# ESP32_with_USBC.net
KiCad netlist of a schematic drawn in Altium Designer
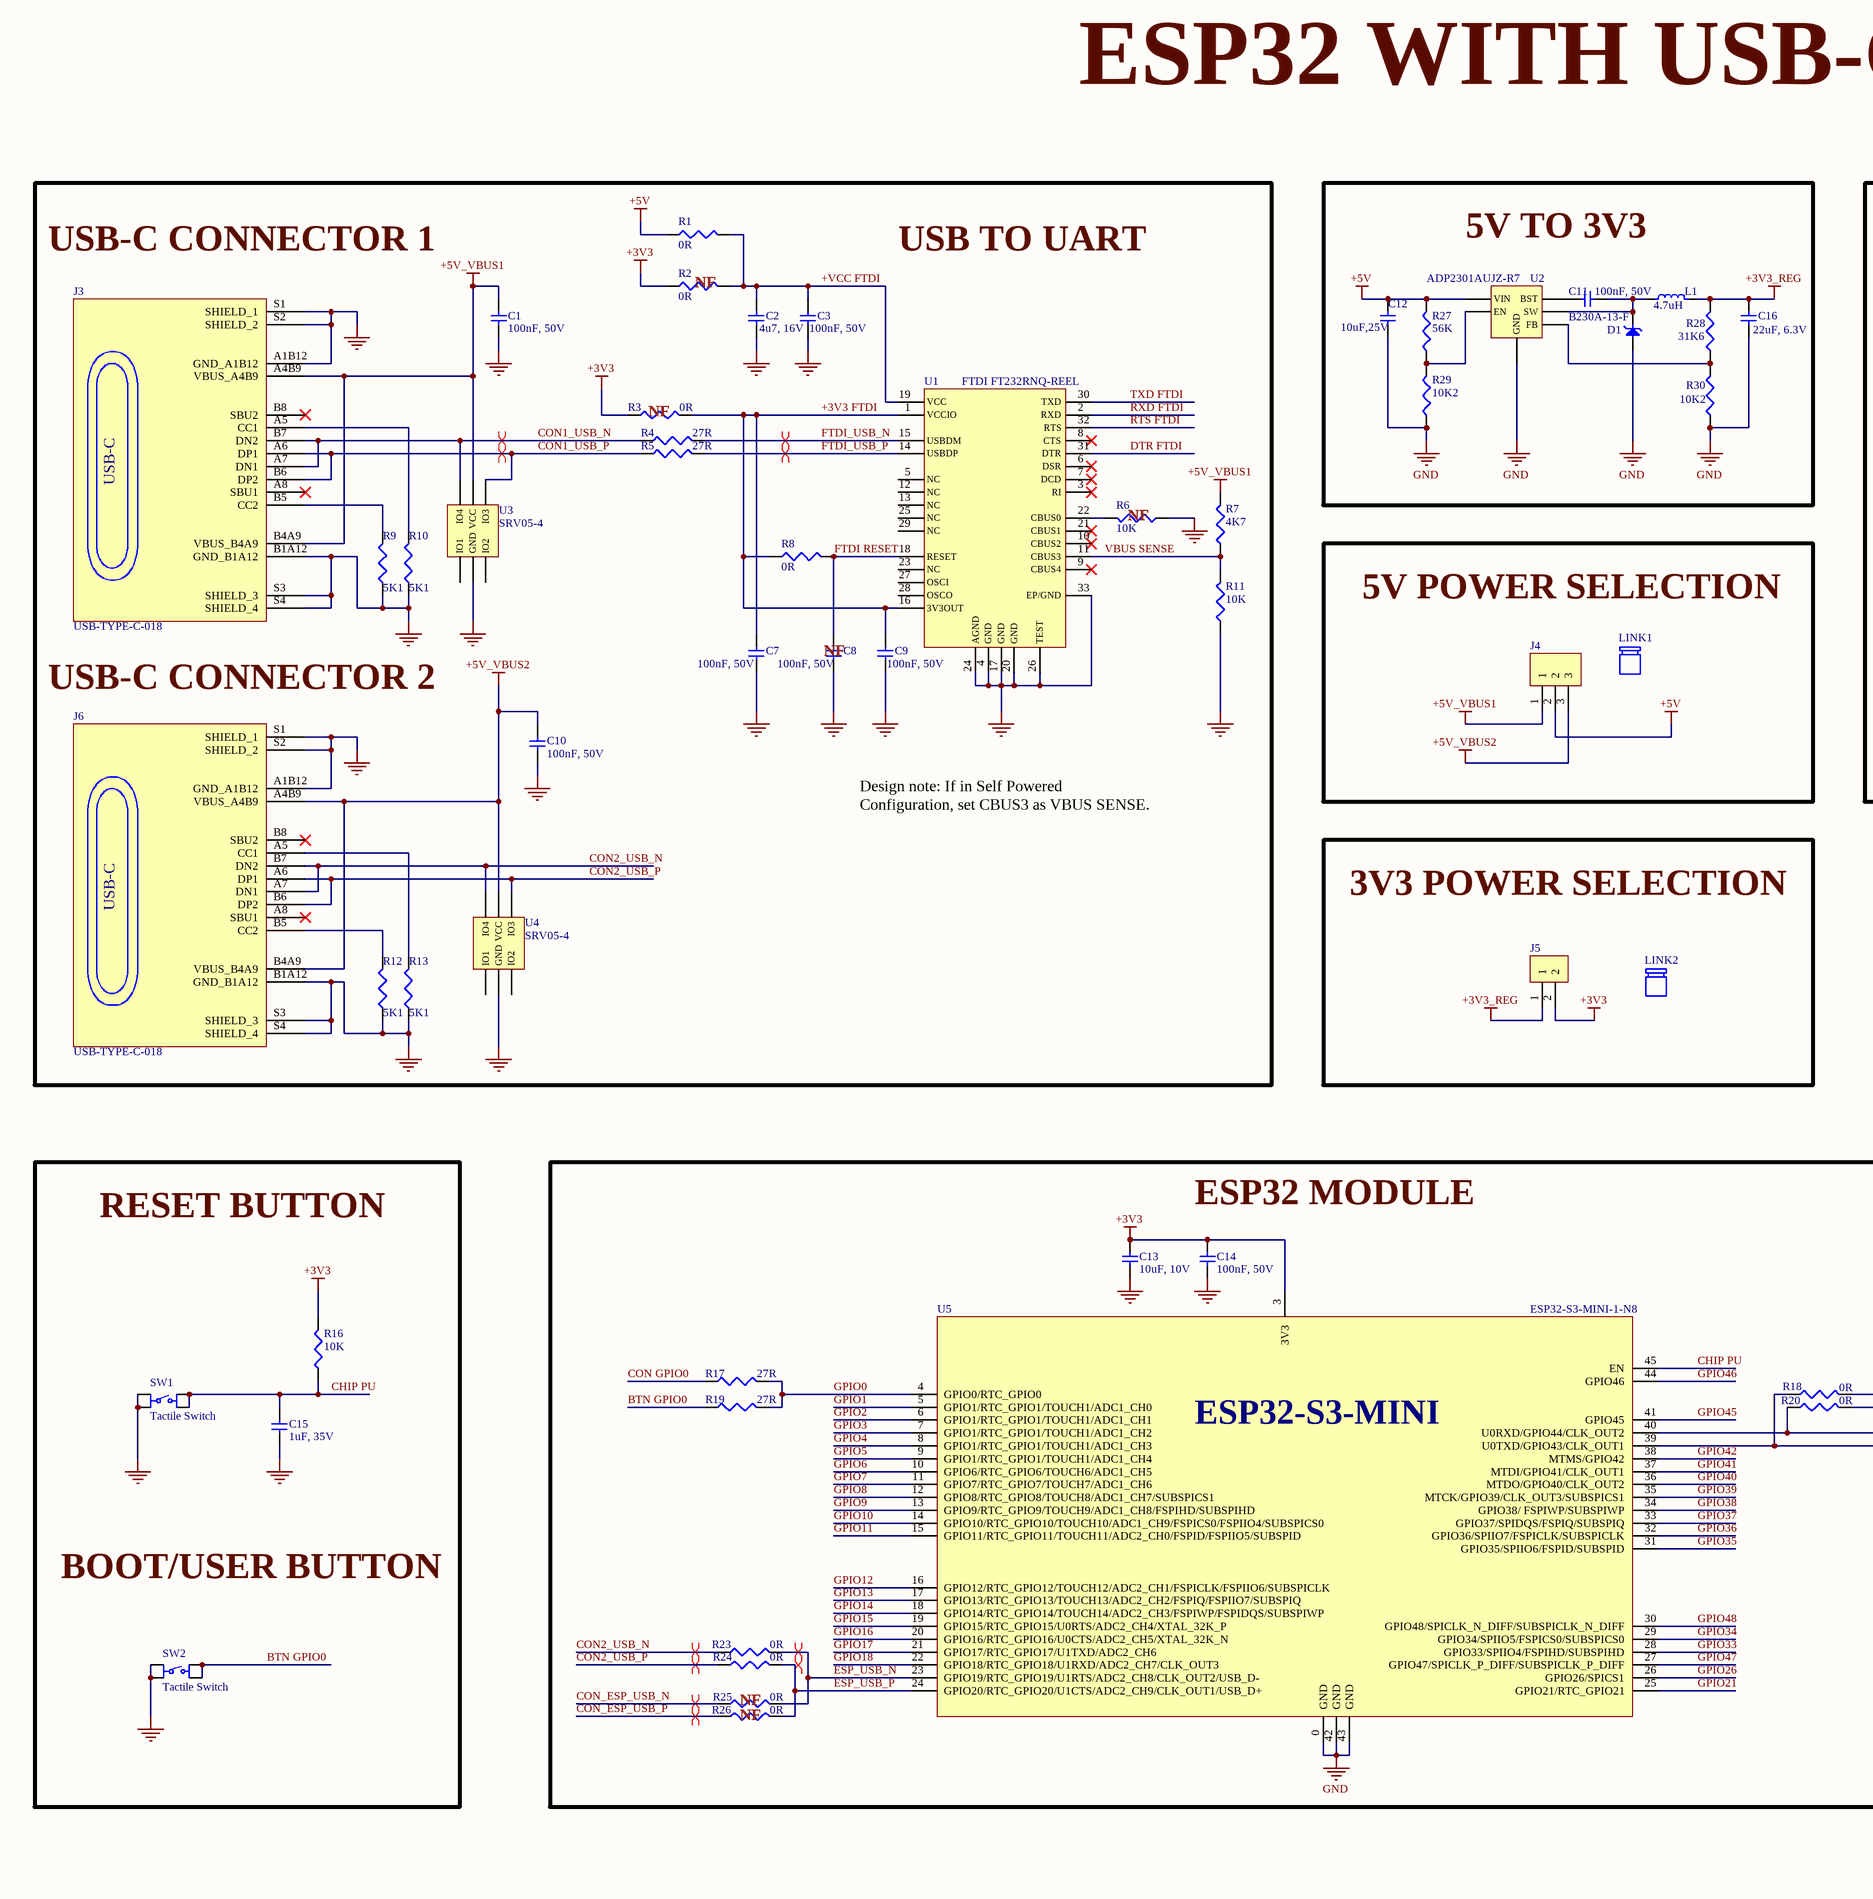
[diagram p0: ESP32 with USBC.SchDoc, left]
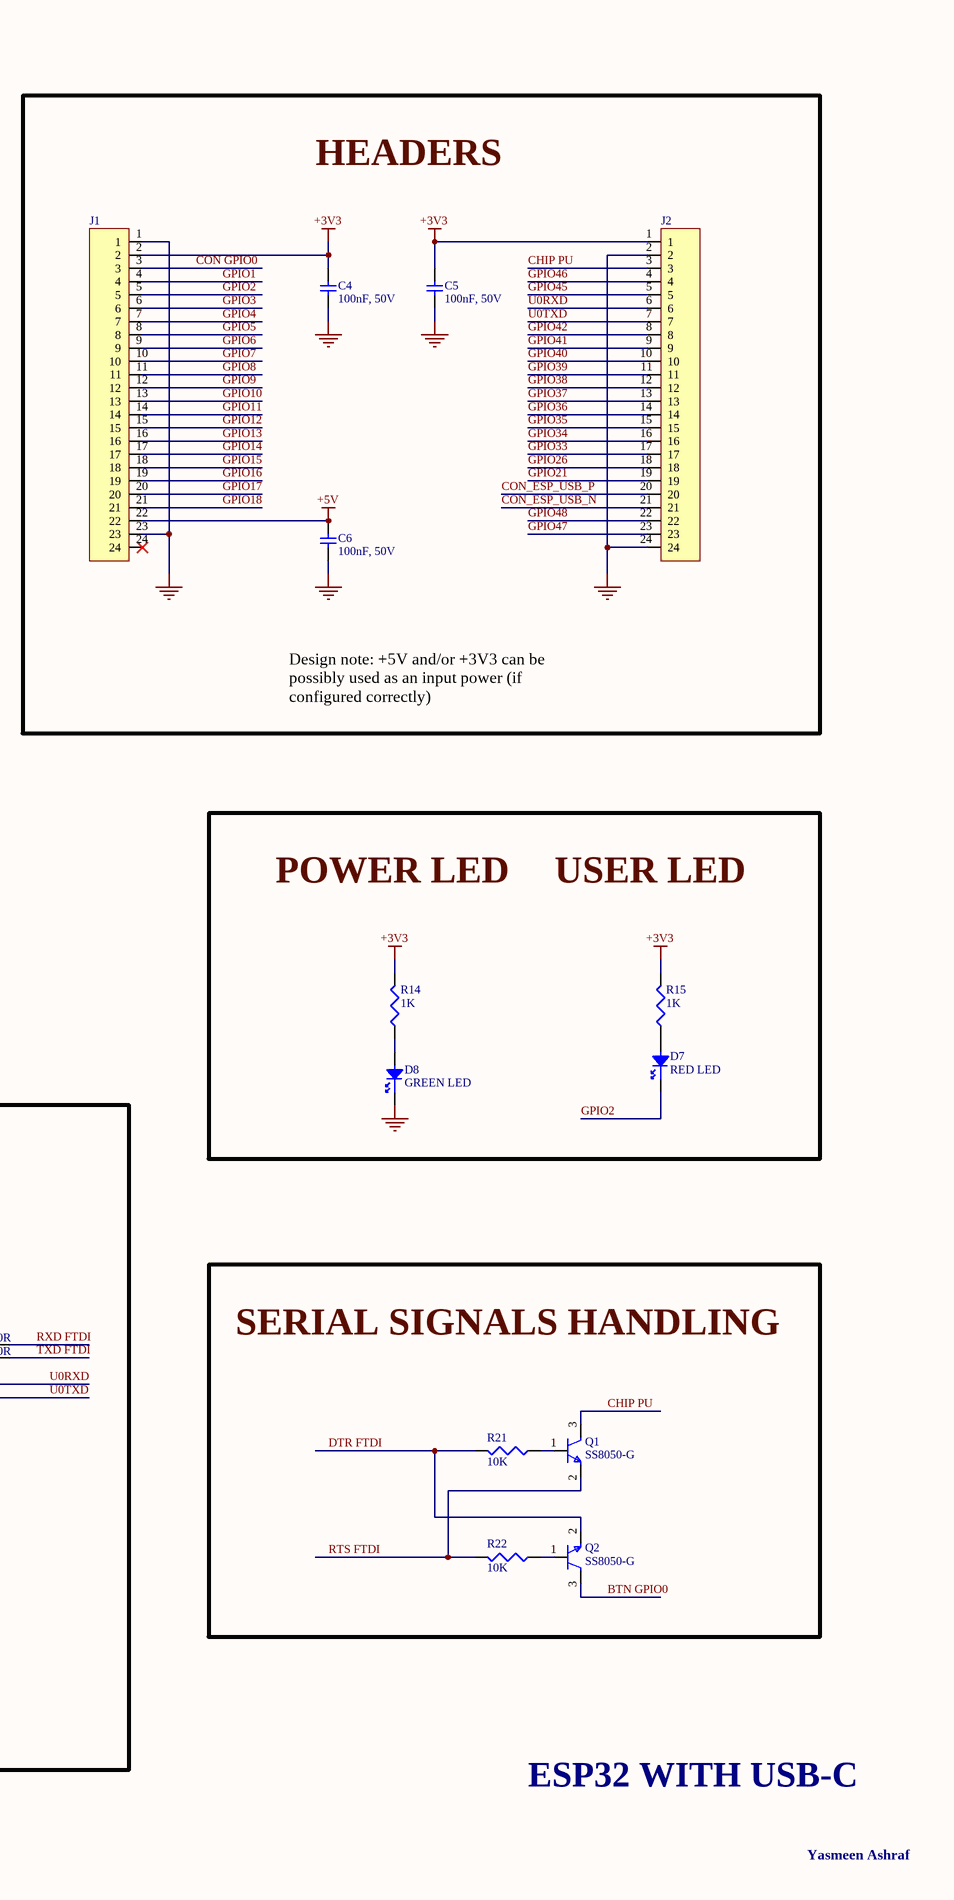
[diagram p1: ESP32 with USBC.SchDoc, right]

(export (version "E")
  (design (tool "Eeschema 10.0.6"))
  (components
    (comp (ref "C1")
      (value "100nF, 50V")
      (footprint "Capacitor")
      (description "50V 100nF X7R ±10% 0402 Multilayer Ceramic Capacitors MLCC - SMD/SMT ROHS")
      (fields
        (field (name "MANUFACTURER") "Samsung")
        (field (name "MANUFACTURER PART NUMBER") "CL05B104KB54PNC")
      )
      (libsource (lib "Schlib1") (part "CL05B104KB54PNC"))
    )
    (comp (ref "C2")
      (value "4u7, 16V")
      (footprint "Capacitor")
      (description "16V 4.7uF X5R ±20% 0402 Multilayer Ceramic Capacitors MLCC - SMD/SMT ROHS")
      (fields
        (field (name "MANUFACTURER") "Samsung Electro-Mechanics")
        (field (name "MANUFACTURER PART NUMBER") "CL05A475MO5NUNC")
      )
      (libsource (lib "Schlib1") (part "CL05A475MO5NUNC"))
    )
    (comp (ref "C3")
      (value "100nF, 50V")
      (footprint "Capacitor")
      (description "50V 100nF X7R ±10% 0402 Multilayer Ceramic Capacitors MLCC - SMD/SMT ROHS")
      (fields
        (field (name "MANUFACTURER") "Samsung")
        (field (name "MANUFACTURER PART NUMBER") "CL05B104KB54PNC")
      )
      (libsource (lib "Schlib1") (part "CL05B104KB54PNC"))
    )
    (comp (ref "C4")
      (value "100nF, 50V")
      (footprint "Capacitor")
      (description "50V 100nF X7R ±10% 0402 Multilayer Ceramic Capacitors MLCC - SMD/SMT ROHS")
      (fields
        (field (name "MANUFACTURER") "Samsung")
        (field (name "MANUFACTURER PART NUMBER") "CL05B104KB54PNC")
      )
      (libsource (lib "Schlib1") (part "CL05B104KB54PNC"))
    )
    (comp (ref "C5")
      (value "100nF, 50V")
      (footprint "Capacitor")
      (description "50V 100nF X7R ±10% 0402 Multilayer Ceramic Capacitors MLCC - SMD/SMT ROHS")
      (fields
        (field (name "MANUFACTURER") "Samsung")
        (field (name "MANUFACTURER PART NUMBER") "CL05B104KB54PNC")
      )
      (libsource (lib "Schlib1") (part "CL05B104KB54PNC"))
    )
    (comp (ref "C6")
      (value "100nF, 50V")
      (footprint "Capacitor")
      (description "50V 100nF X7R ±10% 0402 Multilayer Ceramic Capacitors MLCC - SMD/SMT ROHS")
      (fields
        (field (name "MANUFACTURER") "Samsung")
        (field (name "MANUFACTURER PART NUMBER") "CL05B104KB54PNC")
      )
      (libsource (lib "Schlib1") (part "CL05B104KB54PNC"))
    )
    (comp (ref "C7")
      (value "100nF, 50V")
      (footprint "Capacitor")
      (description "50V 100nF X7R ±10% 0402 Multilayer Ceramic Capacitors MLCC - SMD/SMT ROHS")
      (fields
        (field (name "MANUFACTURER") "Samsung")
        (field (name "MANUFACTURER PART NUMBER") "CL05B104KB54PNC")
      )
      (libsource (lib "Schlib1") (part "CL05B104KB54PNC"))
    )
    (comp (ref "C8")
      (value "100nF, 50V")
      (footprint "Capacitor")
      (description "50V 100nF X7R ±10% 0402 Multilayer Ceramic Capacitors MLCC - SMD/SMT ROHS")
      (fields
        (field (name "MANUFACTURER") "Samsung")
        (field (name "MANUFACTURER PART NUMBER") "CL05B104KB54PNC")
      )
      (libsource (lib "Schlib1") (part "CL05B104KB54PNC"))
    )
    (comp (ref "C9")
      (value "100nF, 50V")
      (footprint "Capacitor")
      (description "50V 100nF X7R ±10% 0402 Multilayer Ceramic Capacitors MLCC - SMD/SMT ROHS")
      (fields
        (field (name "MANUFACTURER") "Samsung")
        (field (name "MANUFACTURER PART NUMBER") "CL05B104KB54PNC")
      )
      (libsource (lib "Schlib1") (part "CL05B104KB54PNC"))
    )
    (comp (ref "C10")
      (value "100nF, 50V")
      (footprint "Capacitor")
      (description "50V 100nF X7R ±10% 0402 Multilayer Ceramic Capacitors MLCC - SMD/SMT ROHS")
      (fields
        (field (name "MANUFACTURER") "Samsung")
        (field (name "MANUFACTURER PART NUMBER") "CL05B104KB54PNC")
      )
      (libsource (lib "Schlib1") (part "CL05B104KB54PNC"))
    )
    (comp (ref "C11")
      (value "100nF, 50V")
      (footprint "Capacitor")
      (description "50V 100nF X7R ±10% 0402 Multilayer Ceramic Capacitors MLCC - SMD/SMT ROHS")
      (fields
        (field (name "MANUFACTURER") "Samsung")
        (field (name "MANUFACTURER PART NUMBER") "CL05B104KB54PNC")
      )
      (libsource (lib "Schlib1") (part "CL05B104KB54PNC"))
    )
    (comp (ref "C12")
      (value "10uF,25V")
      (footprint "CL10A106MA8NRNC")
      (description "25V 10uF X5R ±20% 0603 Multilayer Ceramic Capacitors MLCC - SMD/SMT ROHS")
      (fields
        (field (name "MANUFACTURER") "Samsung Electro-Mechanics")
        (field (name "MANUFACTURER PART NUMBER") "CL10A106MA8NRNC")
      )
      (libsource (lib "Schlib1") (part "CL10A106MA8NRNC"))
    )
    (comp (ref "C13")
      (value "10uF, 10V")
      (footprint "Capacitor")
      (description "10V 10uF X5R ±20% 0402 Multilayer Ceramic Capacitors MLCC - SMD/SMT ROHS")
      (fields
        (field (name "MANUFACTURER") "Samsung")
        (field (name "MANUFACTURER PART NUMBER") "CL05A106MP8NUB8")
      )
      (libsource (lib "Schlib1") (part "CL05A106MP8NUB8"))
    )
    (comp (ref "C14")
      (value "100nF, 50V")
      (footprint "Capacitor")
      (description "50V 100nF X7R ±10% 0402 Multilayer Ceramic Capacitors MLCC - SMD/SMT ROHS")
      (fields
        (field (name "MANUFACTURER") "Samsung")
        (field (name "MANUFACTURER PART NUMBER") "CL05B104KB54PNC")
      )
      (libsource (lib "Schlib1") (part "CL05B104KB54PNC"))
    )
    (comp (ref "C15")
      (value "1uF, 35V")
      (footprint "Capacitor")
      (description "35V 1uF X5R ±10% 0402 Multilayer Ceramic Capacitors MLCC - SMD/SMT ROHS")
      (fields
        (field (name "MANUFACTURER") "Samsung")
        (field (name "MANUFACTURER PART NUMBER") "CL05A105KL5NRNC")
      )
      (libsource (lib "Schlib1") (part "CL05A105KL5NRNC"))
    )
    (comp (ref "C16")
      (value "22uF, 6.3V")
      (footprint "Capacitor")
      (description "6.3V 22uF X5R ±20% 0402 Multilayer Ceramic Capacitors MLCC - SMD/SMT ROHS")
      (fields
        (field (name "MANUFACTURER") "Samsung Electro-Mechanics")
        (field (name "MANUFACTURER PART NUMBER") "CL05A226MQ5QUNC")
      )
      (libsource (lib "Schlib1") (part "CL05A226MQ5QUNC"))
    )
    (comp (ref "D1")
      (value "B230A-13-F")
      (footprint "Schottky Diode")
      (description "30V 500mV@2A 2A SMA(DO-214AC) Schottky Diodes ROHS")
      (fields (field (name "MANUFACTURER") "Diodes Incorporated"))
      (libsource (lib "Schlib1") (part "B230A-13-F"))
    )
    (comp (ref "D7")
      (value "RED LED")
      (footprint "RED LED")
      (description "20mA 54mcd -30℃~+85℃ 631nm Red 130° 75mW 2V 0402 LED Indication - Discrete ROHS")
      (fields (field (name "MANUFACTURE PART NUMBER") "VLMS1500-GS08"))
      (libsource (lib "Schlib1") (part "VLMS1500-GS08"))
    )
    (comp (ref "D8")
      (value "GREEN LED")
      (footprint "GREEN LED")
      (description "20mA 35mcd 571nm Yellow Green 130° 2V 0402 LED Indication - Discrete ROHS")
      (fields (field (name "MANUFACTURE PART NUMBER") "VLMG1500-GS08"))
      (libsource (lib "Schlib1") (part "VLMG1500-GS08"))
    )
    (comp (ref "J1")
      (value "X6511WV-24H-C60D30")
      (footprint "HDR_1x24")
      (libsource (lib "Schlib1") (part "X6511WV-24H-C60D30"))
    )
    (comp (ref "J2")
      (value "X6511WV-24H-C60D30")
      (footprint "HDR_1x24")
      (libsource (lib "") (part "X6511WV-24H-C60D30_1"))
    )
    (comp (ref "J3")
      (value "USB-TYPE-C-018")
      (footprint "USB-TYPE-C-018")
      (description "3A 1 Horizontal attachment 16P Female -25℃~+85℃ Type-C SMD USB Connectors ROHS")
      (libsource (lib "Schlib1") (part "USB-TYPE-C-018"))
    )
    (comp (ref "J4")
      (value "TSW-103-14-G-S")
      (footprint "TSW-103-14-G-S")
      (fields (field (name "MANUFACTURER") "Samtec"))
      (libsource (lib "Schlib1") (part "TSW-103-14-G-S"))
    )
    (comp (ref "J5")
      (value "22284020")
      (footprint "HDR_1x2")
      (description "Direct Insert Policy 2P 2.54mm Single Row Black Brass 1x2P Plugin,P=2.54mm Pin Headers ROHS")
      (libsource (lib "Schlib1") (part "22284020"))
    )
    (comp (ref "J6")
      (value "USB-TYPE-C-018")
      (footprint "USB-TYPE-C-018")
      (description "3A 1 Horizontal attachment 16P Female -25℃~+85℃ Type-C SMD USB Connectors ROHS")
      (libsource (lib "Schlib1") (part "USB-TYPE-C-018"))
    )
    (comp (ref "L1")
      (value "4.7uH")
      (footprint "Inductor")
      (description "2A 4.7uH ±30% 3A SMD,5x5mm Inductors (SMD) ROHS")
      (fields
        (field (name "MANUFACTURER") "Murata Electronics")
        (field (name "MANUFACTURER PART NUMBER") "LQH5BPZ4R7NT0L")
      )
      (libsource (lib "Schlib1") (part "LQH5BPZ4R7NT0L"))
    )
    (comp (ref "LINK1")
      (value "M50-1900005")
      (description "1.27mm (0.05\") Pitch Closed Top Jumper Socket, black, gold")
      (fields (field (name "MANUFACTURER") "Harwin"))
      (libsource (lib "Schlib1") (part "M50-1900005"))
    )
    (comp (ref "LINK2")
      (value "M50-1900005")
      (description "1.27mm (0.05\") Pitch Closed Top Jumper Socket, black, gold")
      (fields (field (name "MANUFACTURER") "Harwin"))
      (libsource (lib "Schlib1") (part "M50-1900005"))
    )
    (comp (ref "Q1")
      (value "SS8050-G")
      (footprint "SS8050-G")
      (description "25V 300mW 120@100mA,1V 1.5A NPN SOT-23 Bipolar (BJT) ROHS")
      (fields (field (name "MANUFACTURE PART NUMBER") "SS8050-G(RANGE:120-200)"))
      (libsource (lib "Schlib1") (part "SS8050-G"))
    )
    (comp (ref "Q2")
      (value "SS8050-G")
      (footprint "SS8050-G")
      (description "25V 300mW 120@100mA,1V 1.5A NPN SOT-23 Bipolar (BJT) ROHS")
      (fields (field (name "MANUFACTURE PART NUMBER") "SS8050-G(RANGE:120-200)"))
      (libsource (lib "Schlib1") (part "SS8050-G"))
    )
    (comp (ref "R1")
      (value "0R")
      (footprint "RC0402")
      (description "62.5mW Thick Film Resistors 50V ±5% 0Ω 0402 Chip Resistor - Surface Mount ROHS")
      (fields
        (field (name "MANUFACTURER") "YAGEO")
        (field (name "MANUFACTURER PART NUMBER") "RC0402JR-070RL")
      )
      (libsource (lib "Schlib1") (part "RC0402JR-070RL"))
    )
    (comp (ref "R2")
      (value "0R")
      (footprint "RC0402")
      (description "62.5mW Thick Film Resistors 50V ±5% 0Ω 0402 Chip Resistor - Surface Mount ROHS")
      (fields
        (field (name "MANUFACTURER") "YAGEO")
        (field (name "MANUFACTURER PART NUMBER") "RC0402JR-070RL")
      )
      (libsource (lib "Schlib1") (part "RC0402JR-070RL"))
    )
    (comp (ref "R3")
      (value "0R")
      (footprint "RC0402")
      (description "62.5mW Thick Film Resistors 50V ±5% 0Ω 0402 Chip Resistor - Surface Mount ROHS")
      (fields
        (field (name "MANUFACTURER") "YAGEO")
        (field (name "MANUFACTURER PART NUMBER") "RC0402JR-070RL")
      )
      (libsource (lib "Schlib1") (part "RC0402JR-070RL"))
    )
    (comp (ref "R4")
      (value "27R")
      (footprint "RC0402")
      (description "62.5mW Thick Film Resistors 50V ±100ppm/℃ ±1% 27Ω 0402 Chip Resistor - Surface Mount ROHS")
      (fields
        (field (name "MANUFACTURER") "Yageo")
        (field (name "MANUFACTURER PART NUMBER") "RC0402FR-0727RL")
      )
      (libsource (lib "Schlib1") (part "RC0402FR-0727RL"))
    )
    (comp (ref "R5")
      (value "27R")
      (footprint "RC0402")
      (description "62.5mW Thick Film Resistors 50V ±100ppm/℃ ±1% 27Ω 0402 Chip Resistor - Surface Mount ROHS")
      (fields
        (field (name "MANUFACTURER") "Yageo")
        (field (name "MANUFACTURER PART NUMBER") "RC0402FR-0727RL")
      )
      (libsource (lib "Schlib1") (part "RC0402FR-0727RL"))
    )
    (comp (ref "R6")
      (value "10K")
      (footprint "AC0402")
      (description "62.5mW Thick Film Resistors 50V ±100ppm/℃ ±1% 10kΩ 0402 Chip Resistor - Surface Mount ROHS")
      (fields
        (field (name "MANUFACTURER") "Yageo")
        (field (name "MANUFACTURER PART NUMBER") "AC0402FR-0710KL")
      )
      (libsource (lib "Schlib1") (part "AC0402FR-0710KL"))
    )
    (comp (ref "R7")
      (value "4K7")
      (footprint "RC0402")
      (description "62.5mW Thick Film Resistors 50V ±100ppm/℃ ±1% 4.7kΩ 0402 Chip Resistor - Surface Mount ROHS")
      (fields
        (field (name "MANUFACTURER") "YAGEO")
        (field (name "MANUFACTURER PART NUMBER") "RC0402FR-074K7L")
      )
      (libsource (lib "Schlib1") (part "RC0402FR-074K7L"))
    )
    (comp (ref "R8")
      (value "0R")
      (footprint "RC0402")
      (description "62.5mW Thick Film Resistors 50V ±5% 0Ω 0402 Chip Resistor - Surface Mount ROHS")
      (fields
        (field (name "MANUFACTURER") "YAGEO")
        (field (name "MANUFACTURER PART NUMBER") "RC0402JR-070RL")
      )
      (libsource (lib "Schlib1") (part "RC0402JR-070RL"))
    )
    (comp (ref "R9")
      (value "5K1")
      (footprint "RC0402")
      (description "62.5mW Thick Film Resistors 50V ±100ppm/℃ ±1% 5.1kΩ 0402 Chip Resistor - Surface Mount ROHS")
      (fields
        (field (name "MANUFACTURER") "Yageo")
        (field (name "MANUFACTURER PART NUMBER") "RC0402FR-075K1L")
      )
      (libsource (lib "Schlib1") (part "RC0402FR-075K1L"))
    )
    (comp (ref "R10")
      (value "5K1")
      (footprint "RC0402")
      (description "62.5mW Thick Film Resistors 50V ±100ppm/℃ ±1% 5.1kΩ 0402 Chip Resistor - Surface Mount ROHS")
      (fields
        (field (name "MANUFACTURER") "Yageo")
        (field (name "MANUFACTURER PART NUMBER") "RC0402FR-075K1L")
      )
      (libsource (lib "Schlib1") (part "RC0402FR-075K1L"))
    )
    (comp (ref "R11")
      (value "10K")
      (footprint "AC0402")
      (description "62.5mW Thick Film Resistors 50V ±100ppm/℃ ±1% 10kΩ 0402 Chip Resistor - Surface Mount ROHS")
      (fields
        (field (name "MANUFACTURER") "Yageo")
        (field (name "MANUFACTURER PART NUMBER") "AC0402FR-0710KL")
      )
      (libsource (lib "Schlib1") (part "AC0402FR-0710KL"))
    )
    (comp (ref "R12")
      (value "5K1")
      (footprint "RC0402")
      (description "62.5mW Thick Film Resistors 50V ±100ppm/℃ ±1% 5.1kΩ 0402 Chip Resistor - Surface Mount ROHS")
      (fields
        (field (name "MANUFACTURER") "Yageo")
        (field (name "MANUFACTURER PART NUMBER") "RC0402FR-075K1L")
      )
      (libsource (lib "Schlib1") (part "RC0402FR-075K1L"))
    )
    (comp (ref "R13")
      (value "5K1")
      (footprint "RC0402")
      (description "62.5mW Thick Film Resistors 50V ±100ppm/℃ ±1% 5.1kΩ 0402 Chip Resistor - Surface Mount ROHS")
      (fields
        (field (name "MANUFACTURER") "Yageo")
        (field (name "MANUFACTURER PART NUMBER") "RC0402FR-075K1L")
      )
      (libsource (lib "Schlib1") (part "RC0402FR-075K1L"))
    )
    (comp (ref "R14")
      (value "1K")
      (footprint "RC0402")
      (description "62.5mW Thick Film Resistors 50V ±100ppm/℃ ±1% 1kΩ 0402 Chip Resistor - Surface Mount ROHS")
      (fields
        (field (name "MANUFACTURER") "YAGEO")
        (field (name "MANUFACTURER PART NUMBER") "RC0402FR-071KL")
      )
      (libsource (lib "Schlib1") (part "RC0402FR-071KL"))
    )
    (comp (ref "R15")
      (value "1K")
      (footprint "RC0402")
      (description "62.5mW Thick Film Resistors 50V ±100ppm/℃ ±1% 1kΩ 0402 Chip Resistor - Surface Mount ROHS")
      (fields
        (field (name "MANUFACTURER") "YAGEO")
        (field (name "MANUFACTURER PART NUMBER") "RC0402FR-071KL")
      )
      (libsource (lib "Schlib1") (part "RC0402FR-071KL"))
    )
    (comp (ref "R16")
      (value "10K")
      (footprint "AC0402")
      (description "62.5mW Thick Film Resistors 50V ±100ppm/℃ ±1% 10kΩ 0402 Chip Resistor - Surface Mount ROHS")
      (fields
        (field (name "MANUFACTURER") "Yageo")
        (field (name "MANUFACTURER PART NUMBER") "AC0402FR-0710KL")
      )
      (libsource (lib "Schlib1") (part "AC0402FR-0710KL"))
    )
    (comp (ref "R17")
      (value "27R")
      (footprint "RC0402")
      (description "62.5mW Thick Film Resistors 50V ±100ppm/℃ ±1% 27Ω 0402 Chip Resistor - Surface Mount ROHS")
      (fields
        (field (name "MANUFACTURER") "Yageo")
        (field (name "MANUFACTURER PART NUMBER") "RC0402FR-0727RL")
      )
      (libsource (lib "Schlib1") (part "RC0402FR-0727RL"))
    )
    (comp (ref "R18")
      (value "0R")
      (footprint "RC0402")
      (description "62.5mW Thick Film Resistors 50V ±5% 0Ω 0402 Chip Resistor - Surface Mount ROHS")
      (fields
        (field (name "MANUFACTURER") "YAGEO")
        (field (name "MANUFACTURER PART NUMBER") "RC0402JR-070RL")
      )
      (libsource (lib "Schlib1") (part "RC0402JR-070RL"))
    )
    (comp (ref "R19")
      (value "27R")
      (footprint "RC0402")
      (description "62.5mW Thick Film Resistors 50V ±100ppm/℃ ±1% 27Ω 0402 Chip Resistor - Surface Mount ROHS")
      (fields
        (field (name "MANUFACTURER") "Yageo")
        (field (name "MANUFACTURER PART NUMBER") "RC0402FR-0727RL")
      )
      (libsource (lib "Schlib1") (part "RC0402FR-0727RL"))
    )
    (comp (ref "R20")
      (value "0R")
      (footprint "RC0402")
      (description "62.5mW Thick Film Resistors 50V ±5% 0Ω 0402 Chip Resistor - Surface Mount ROHS")
      (fields
        (field (name "MANUFACTURER") "YAGEO")
        (field (name "MANUFACTURER PART NUMBER") "RC0402JR-070RL")
      )
      (libsource (lib "Schlib1") (part "RC0402JR-070RL"))
    )
    (comp (ref "R21")
      (value "10K")
      (footprint "AC0402")
      (description "62.5mW Thick Film Resistors 50V ±100ppm/℃ ±1% 10kΩ 0402 Chip Resistor - Surface Mount ROHS")
      (fields
        (field (name "MANUFACTURER") "Yageo")
        (field (name "MANUFACTURER PART NUMBER") "AC0402FR-0710KL")
      )
      (libsource (lib "Schlib1") (part "AC0402FR-0710KL"))
    )
    (comp (ref "R22")
      (value "10K")
      (footprint "AC0402")
      (description "62.5mW Thick Film Resistors 50V ±100ppm/℃ ±1% 10kΩ 0402 Chip Resistor - Surface Mount ROHS")
      (fields
        (field (name "MANUFACTURER") "Yageo")
        (field (name "MANUFACTURER PART NUMBER") "AC0402FR-0710KL")
      )
      (libsource (lib "Schlib1") (part "AC0402FR-0710KL"))
    )
    (comp (ref "R23")
      (value "0R")
      (footprint "RC0402")
      (description "62.5mW Thick Film Resistors 50V ±5% 0Ω 0402 Chip Resistor - Surface Mount ROHS")
      (fields
        (field (name "MANUFACTURER") "YAGEO")
        (field (name "MANUFACTURER PART NUMBER") "RC0402JR-070RL")
      )
      (libsource (lib "Schlib1") (part "RC0402JR-070RL"))
    )
    (comp (ref "R24")
      (value "0R")
      (footprint "RC0402")
      (description "62.5mW Thick Film Resistors 50V ±5% 0Ω 0402 Chip Resistor - Surface Mount ROHS")
      (fields
        (field (name "MANUFACTURER") "YAGEO")
        (field (name "MANUFACTURER PART NUMBER") "RC0402JR-070RL")
      )
      (libsource (lib "Schlib1") (part "RC0402JR-070RL"))
    )
    (comp (ref "R25")
      (value "0R")
      (footprint "RC0402")
      (description "62.5mW Thick Film Resistors 50V ±5% 0Ω 0402 Chip Resistor - Surface Mount ROHS")
      (fields
        (field (name "MANUFACTURER") "YAGEO")
        (field (name "MANUFACTURER PART NUMBER") "RC0402JR-070RL")
      )
      (libsource (lib "Schlib1") (part "RC0402JR-070RL"))
    )
    (comp (ref "R26")
      (value "0R")
      (footprint "RC0402")
      (description "62.5mW Thick Film Resistors 50V ±5% 0Ω 0402 Chip Resistor - Surface Mount ROHS")
      (fields
        (field (name "MANUFACTURER") "YAGEO")
        (field (name "MANUFACTURER PART NUMBER") "RC0402JR-070RL")
      )
      (libsource (lib "Schlib1") (part "RC0402JR-070RL"))
    )
    (comp (ref "R27")
      (value "56K")
      (footprint "RC0402")
      (description "62.5mW Thick Film Resistors 50V ±100ppm/℃ ±1% 56kΩ 0402 Chip Resistor - Surface Mount ROHS")
      (fields
        (field (name "MANUFACTURER") "YAGEO")
        (field (name "MANUFACTURER PART NUMBER") "RC0402FR-0756KL")
      )
      (libsource (lib "Schlib1") (part "RC0402FR-0756KL"))
    )
    (comp (ref "R28")
      (value "31K6")
      (footprint "AC0402")
      (description "62.5mW Thick Film Resistors 50V ±100ppm/℃ ±1% 31.6kΩ 0402 Chip Resistor - Surface Mount ROHS")
      (fields
        (field (name "MANUFACTURER") "YAGEO")
        (field (name "MANUFACTURER PART NUMBER") "AC0402FR-0731K6L")
      )
      (libsource (lib "Schlib1") (part "AC0402FR-0731K6L"))
    )
    (comp (ref "R29")
      (value "10K2")
      (footprint "RC0402")
      (description "62.5mW Thick Film Resistors 50V ±100ppm/℃ ±1% 10.2kΩ 0402 Chip Resistor - Surface Mount ROHS")
      (fields
        (field (name "MANUFACTURER") "YAGEO")
        (field (name "MANUFACTURER PART NUMBER") "RC0402FR-0710K2L")
      )
      (libsource (lib "Schlib1") (part "RC0402FR-0710K2L"))
    )
    (comp (ref "R30")
      (value "10K2")
      (footprint "RC0402")
      (description "62.5mW Thick Film Resistors 50V ±100ppm/℃ ±1% 10.2kΩ 0402 Chip Resistor - Surface Mount ROHS")
      (fields
        (field (name "MANUFACTURER") "YAGEO")
        (field (name "MANUFACTURER PART NUMBER") "RC0402FR-0710K2L")
      )
      (libsource (lib "Schlib1") (part "RC0402FR-0710K2L"))
    )
    (comp (ref "SW1")
      (value "Tactile Switch")
      (footprint "Tactile Switch")
      (fields (field (name "MANUFACTURE PART NUMBER") "PTS525SM15SMTR2LFS"))
      (libsource (lib "Schlib1") (part "Tactile Switch"))
    )
    (comp (ref "SW2")
      (value "Tactile Switch")
      (footprint "Tactile Switch")
      (fields (field (name "MANUFACTURE PART NUMBER") "PTS525SM15SMTR2LFS"))
      (libsource (lib "Schlib1") (part "Tactile Switch"))
    )
    (comp (ref "U1")
      (value "FTDI FT232RNQ-REEL")
      (footprint "FTDI FT232RNQ-REEL")
      (description "USB to UART QFN-32(5x5) USB Converters ROHS")
      (fields (field (name "MANUFACTURER") "FTDI") (field (name "MANUFACTURER PART NUMBER") "FT232RNQ-REEL"))
      (libsource (lib "Schlib1") (part "FTDI FT232RNQ-REEL"))
    )
    (comp (ref "U2")
      (value "ADP2301AUJZ-R7")
      (footprint "BUCK")
      (description "Step-down type Adjustable 800mV~17V 1.2A 3V~20V TSOT-6 DC-DC Converters ROHS")
      (fields (field (name "MANUFACTURER") "Analog Devices"))
      (libsource (lib "Schlib1") (part "ADP2301AUJZ-R7"))
    )
    (comp (ref "U3")
      (value "SRV05-4")
      (footprint "SRV05-4")
      (description "15V 60W 9V 5V SOT-23-6 ESD and Surge Protection (TVS/ESD) ROHS")
      (libsource (lib "Schlib1") (part "SRV05-4"))
    )
    (comp (ref "U4")
      (value "SRV05-4")
      (footprint "SRV05-4")
      (description "15V 60W 9V 5V SOT-23-6 ESD and Surge Protection (TVS/ESD) ROHS")
      (libsource (lib "Schlib1") (part "SRV05-4"))
    )
    (comp (ref "U5")
      (value "ESP32-S3-MINI-1-N8")
      (footprint "ESP32-S3-MINI-1-N8")
      (description "SMD module, ESP32-S3FN8, 8 MB SPI flash, PCB antenna")
      (fields (field (name "MANUFACTURER") "Espressif Systems"))
      (libsource (lib "Schlib1") (part "ESP32-S3-MINI-1-N8"))
    )
  )
  (nets
    (net (code "1") (name "+3V3") (class "Default")
      (node (ref "C13") (pin "2") (pinfunction "2_2") (pintype "passive"))
      (node (ref "C14") (pin "2") (pinfunction "2_2") (pintype "passive"))
      (node (ref "C4") (pin "2") (pinfunction "2_2") (pintype "passive"))
      (node (ref "C5") (pin "2") (pinfunction "2_2") (pintype "passive"))
      (node (ref "J1") (pin "2") (pinfunction "2_2") (pintype "passive"))
      (node (ref "J2") (pin "1") (pinfunction "1_1") (pintype "passive"))
      (node (ref "J5") (pin "2") (pinfunction "2_2") (pintype "passive"))
      (node (ref "R14") (pin "2") (pinfunction "2_2") (pintype "passive"))
      (node (ref "R15") (pin "2") (pinfunction "2_2") (pintype "passive"))
      (node (ref "R16") (pin "2") (pinfunction "2_2") (pintype "passive"))
      (node (ref "R2") (pin "1") (pinfunction "1_1") (pintype "passive"))
      (node (ref "R3") (pin "1") (pinfunction "1_1") (pintype "passive"))
      (node (ref "U5") (pin "3") (pinfunction "3V3_3") (pintype "passive"))
    )
    (net (code "2") (name "+3V3_REG") (class "Default")
      (node (ref "C16") (pin "2") (pinfunction "2_2") (pintype "passive"))
      (node (ref "J5") (pin "1") (pinfunction "1_1") (pintype "passive"))
      (node (ref "L1") (pin "2") (pinfunction "2_2") (pintype "passive"))
      (node (ref "R28") (pin "2") (pinfunction "2_2") (pintype "passive"))
    )
    (net (code "3") (name "+5V") (class "Default")
      (node (ref "C12") (pin "2") (pinfunction "2_2") (pintype "passive"))
      (node (ref "C6") (pin "2") (pinfunction "2_2") (pintype "passive"))
      (node (ref "J1") (pin "22") (pinfunction "22_22") (pintype "passive"))
      (node (ref "J4") (pin "2") (pinfunction "2_2") (pintype "passive"))
      (node (ref "R1") (pin "1") (pinfunction "1_1") (pintype "passive"))
      (node (ref "R27") (pin "2") (pinfunction "2_2") (pintype "passive"))
      (node (ref "U2") (pin "5") (pinfunction "VIN_5") (pintype "passive"))
    )
    (net (code "4") (name "+5V_VBUS1") (class "Default")
      (node (ref "C1") (pin "2") (pinfunction "2_2") (pintype "passive"))
      (node (ref "J3") (pin "A4B9") (pinfunction "VBUS_A4B9_A4B9") (pintype "passive"))
      (node (ref "J3") (pin "B4A9") (pinfunction "VBUS_B4A9_B4A9") (pintype "passive"))
      (node (ref "J4") (pin "1") (pinfunction "1_1") (pintype "passive"))
      (node (ref "R7") (pin "2") (pinfunction "2_2") (pintype "passive"))
      (node (ref "U3") (pin "5") (pinfunction "VCC_5") (pintype "passive"))
    )
    (net (code "5") (name "+5V_VBUS2") (class "Default")
      (node (ref "C10") (pin "2") (pinfunction "2_2") (pintype "passive"))
      (node (ref "J4") (pin "3") (pinfunction "3_3") (pintype "passive"))
      (node (ref "J6") (pin "A4B9") (pinfunction "VBUS_A4B9_A4B9") (pintype "passive"))
      (node (ref "J6") (pin "B4A9") (pinfunction "VBUS_B4A9_B4A9") (pintype "passive"))
      (node (ref "U4") (pin "5") (pinfunction "VCC_5") (pintype "passive"))
    )
    (net (code "6") (name "/+3V3 FTDI") (class "Default")
      (node (ref "C7") (pin "2") (pinfunction "2_2") (pintype "passive"))
      (node (ref "C9") (pin "2") (pinfunction "2_2") (pintype "passive"))
      (node (ref "R3") (pin "2") (pinfunction "2_2") (pintype "passive"))
      (node (ref "R8") (pin "1") (pinfunction "1_1") (pintype "passive"))
      (node (ref "U1") (pin "1") (pinfunction "VCCIO_1") (pintype "passive"))
      (node (ref "U1") (pin "16") (pinfunction "3V3OUT_16") (pintype "passive"))
    )
    (net (code "7") (name "/+VCC FTDI") (class "Default")
      (node (ref "C2") (pin "2") (pinfunction "2_2") (pintype "passive"))
      (node (ref "C3") (pin "2") (pinfunction "2_2") (pintype "passive"))
      (node (ref "R1") (pin "2") (pinfunction "2_2") (pintype "passive"))
      (node (ref "R2") (pin "2") (pinfunction "2_2") (pintype "passive"))
      (node (ref "U1") (pin "19") (pinfunction "VCC_19") (pintype "passive"))
    )
    (net (code "8") (name "/BTN GPIO0") (class "Default")
      (node (ref "Q2") (pin "3") (pinfunction "3_3") (pintype "passive"))
      (node (ref "R19") (pin "1") (pinfunction "1_1") (pintype "passive"))
      (node (ref "SW2") (pin "1") (pinfunction "1_1") (pintype "passive"))
      (node (ref "SW2") (pin "2") (pinfunction "2_2") (pintype "passive"))
    )
    (net (code "9") (name "/CHIP PU") (class "Default")
      (node (ref "C15") (pin "2") (pinfunction "2_2") (pintype "passive"))
      (node (ref "J2") (pin "3") (pinfunction "3_3") (pintype "passive"))
      (node (ref "Q1") (pin "3") (pinfunction "3_3") (pintype "passive"))
      (node (ref "R16") (pin "1") (pinfunction "1_1") (pintype "passive"))
      (node (ref "SW1") (pin "1") (pinfunction "1_1") (pintype "passive"))
      (node (ref "SW1") (pin "2") (pinfunction "2_2") (pintype "passive"))
      (node (ref "U5") (pin "45") (pinfunction "EN_45") (pintype "passive"))
    )
    (net (code "10") (name "/CON GPIO0") (class "Default")
      (node (ref "J1") (pin "3") (pinfunction "3_3") (pintype "passive"))
      (node (ref "R17") (pin "1") (pinfunction "1_1") (pintype "passive"))
    )
    (net (code "11") (name "/CON1_USB_N") (class "Default")
      (node (ref "J3") (pin "A7") (pinfunction "DN1_A7") (pintype "passive"))
      (node (ref "J3") (pin "B7") (pinfunction "DN2_B7") (pintype "passive"))
      (node (ref "R4") (pin "1") (pinfunction "1_1") (pintype "passive"))
      (node (ref "U3") (pin "6") (pinfunction "IO4_6") (pintype "passive"))
    )
    (net (code "12") (name "/CON1_USB_P") (class "Default")
      (node (ref "J3") (pin "A6") (pinfunction "DP1_A6") (pintype "passive"))
      (node (ref "J3") (pin "B6") (pinfunction "DP2_B6") (pintype "passive"))
      (node (ref "R5") (pin "1") (pinfunction "1_1") (pintype "passive"))
      (node (ref "U3") (pin "4") (pinfunction "IO3_4") (pintype "passive"))
    )
    (net (code "13") (name "/CON2_USB_N") (class "Default")
      (node (ref "J6") (pin "A7") (pinfunction "DN1_A7") (pintype "passive"))
      (node (ref "J6") (pin "B7") (pinfunction "DN2_B7") (pintype "passive"))
      (node (ref "R23") (pin "1") (pinfunction "1_1") (pintype "passive"))
      (node (ref "U4") (pin "6") (pinfunction "IO4_6") (pintype "passive"))
    )
    (net (code "14") (name "/CON2_USB_P") (class "Default")
      (node (ref "J6") (pin "A6") (pinfunction "DP1_A6") (pintype "passive"))
      (node (ref "J6") (pin "B6") (pinfunction "DP2_B6") (pintype "passive"))
      (node (ref "R24") (pin "1") (pinfunction "1_1") (pintype "passive"))
      (node (ref "U4") (pin "4") (pinfunction "IO3_4") (pintype "passive"))
    )
    (net (code "15") (name "/CON_ESP_USB_N") (class "Default")
      (node (ref "J2") (pin "21") (pinfunction "21_21") (pintype "passive"))
      (node (ref "R25") (pin "1") (pinfunction "1_1") (pintype "passive"))
    )
    (net (code "16") (name "/CON_ESP_USB_P") (class "Default")
      (node (ref "J2") (pin "20") (pinfunction "20_20") (pintype "passive"))
      (node (ref "R26") (pin "1") (pinfunction "1_1") (pintype "passive"))
    )
    (net (code "17") (name "/DTR FTDI") (class "Default")
      (node (ref "Q2") (pin "2") (pinfunction "2_2") (pintype "passive"))
      (node (ref "R21") (pin "2") (pinfunction "2_2") (pintype "passive"))
      (node (ref "U1") (pin "31") (pinfunction "DTR_31") (pintype "passive"))
    )
    (net (code "18") (name "/ESP_USB_N") (class "Default")
      (node (ref "R23") (pin "2") (pinfunction "2_2") (pintype "passive"))
      (node (ref "R25") (pin "2") (pinfunction "2_2") (pintype "passive"))
      (node (ref "U5") (pin "23") (pinfunction "GPIO19/RTC_GPIO19/U1RTS/ADC2_CH8/CLK_OUT2/USB_D-_23") (pintype "passive"))
    )
    (net (code "19") (name "/ESP_USB_P") (class "Default")
      (node (ref "R24") (pin "2") (pinfunction "2_2") (pintype "passive"))
      (node (ref "R26") (pin "2") (pinfunction "2_2") (pintype "passive"))
      (node (ref "U5") (pin "24") (pinfunction "GPIO20/RTC_GPIO20/U1CTS/ADC2_CH9/CLK_OUT1/USB_D+_24") (pintype "passive"))
    )
    (net (code "20") (name "/FTDI RESET") (class "Default")
      (node (ref "C8") (pin "2") (pinfunction "2_2") (pintype "passive"))
      (node (ref "R8") (pin "2") (pinfunction "2_2") (pintype "passive"))
      (node (ref "U1") (pin "18") (pinfunction "RESET_18") (pintype "passive"))
    )
    (net (code "21") (name "/FTDI_USB_N") (class "Default")
      (node (ref "R4") (pin "2") (pinfunction "2_2") (pintype "passive"))
      (node (ref "U1") (pin "15") (pinfunction "USBDM_15") (pintype "passive"))
    )
    (net (code "22") (name "/FTDI_USB_P") (class "Default")
      (node (ref "R5") (pin "2") (pinfunction "2_2") (pintype "passive"))
      (node (ref "U1") (pin "14") (pinfunction "USBDP_14") (pintype "passive"))
    )
    (net (code "23") (name "/GPIO0") (class "Default")
      (node (ref "R17") (pin "2") (pinfunction "2_2") (pintype "passive"))
      (node (ref "R19") (pin "2") (pinfunction "2_2") (pintype "passive"))
      (node (ref "U5") (pin "4") (pinfunction "GPIO0/RTC_GPIO0_4") (pintype "passive"))
    )
    (net (code "24") (name "/GPIO1") (class "Default")
      (node (ref "J1") (pin "4") (pinfunction "4_4") (pintype "passive"))
      (node (ref "U5") (pin "5") (pinfunction "GPIO1/RTC_GPIO1/TOUCH1/ADC1_CH0_5") (pintype "passive"))
    )
    (net (code "25") (name "/GPIO2") (class "Default")
      (node (ref "D7") (pin "1") (pinfunction "1_1") (pintype "passive"))
      (node (ref "J1") (pin "5") (pinfunction "5_5") (pintype "passive"))
      (node (ref "U5") (pin "6") (pinfunction "GPIO1/RTC_GPIO1/TOUCH1/ADC1_CH1_6") (pintype "passive"))
    )
    (net (code "26") (name "/GPIO3") (class "Default")
      (node (ref "J1") (pin "6") (pinfunction "6_6") (pintype "passive"))
      (node (ref "U5") (pin "7") (pinfunction "GPIO1/RTC_GPIO1/TOUCH1/ADC1_CH2_7") (pintype "passive"))
    )
    (net (code "27") (name "/GPIO4") (class "Default")
      (node (ref "J1") (pin "7") (pinfunction "7_7") (pintype "passive"))
      (node (ref "U5") (pin "8") (pinfunction "GPIO1/RTC_GPIO1/TOUCH1/ADC1_CH3_8") (pintype "passive"))
    )
    (net (code "28") (name "/GPIO5") (class "Default")
      (node (ref "J1") (pin "8") (pinfunction "8_8") (pintype "passive"))
      (node (ref "U5") (pin "9") (pinfunction "GPIO1/RTC_GPIO1/TOUCH1/ADC1_CH4_9") (pintype "passive"))
    )
    (net (code "29") (name "/GPIO6") (class "Default")
      (node (ref "J1") (pin "9") (pinfunction "9_9") (pintype "passive"))
      (node (ref "U5") (pin "10") (pinfunction "GPIO6/RTC_GPIO6/TOUCH6/ADC1_CH5_10") (pintype "passive"))
    )
    (net (code "30") (name "/GPIO7") (class "Default")
      (node (ref "J1") (pin "10") (pinfunction "10_10") (pintype "passive"))
      (node (ref "U5") (pin "11") (pinfunction "GPIO7/RTC_GPIO7/TOUCH7/ADC1_CH6_11") (pintype "passive"))
    )
    (net (code "31") (name "/GPIO8") (class "Default")
      (node (ref "J1") (pin "11") (pinfunction "11_11") (pintype "passive"))
      (node (ref "U5") (pin "12") (pinfunction "GPIO8/RTC_GPIO8/TOUCH8/ADC1_CH7/SUBSPICS1_12") (pintype "passive"))
    )
    (net (code "32") (name "/GPIO9") (class "Default")
      (node (ref "J1") (pin "12") (pinfunction "12_12") (pintype "passive"))
      (node (ref "U5") (pin "13") (pinfunction "GPIO9/RTC_GPIO9/TOUCH9/ADC1_CH8/FSPIHD/SUBSPIHD_13") (pintype "passive"))
    )
    (net (code "33") (name "/GPIO10") (class "Default")
      (node (ref "J1") (pin "13") (pinfunction "13_13") (pintype "passive"))
      (node (ref "U5") (pin "14") (pinfunction "GPIO10/RTC_GPIO10/TOUCH10/ADC1_CH9/FSPICS0/FSPIIO4/SUBSPICS0_14") (pintype "passive"))
    )
    (net (code "34") (name "/GPIO11") (class "Default")
      (node (ref "J1") (pin "14") (pinfunction "14_14") (pintype "passive"))
      (node (ref "U5") (pin "15") (pinfunction "GPIO11/RTC_GPIO11/TOUCH11/ADC2_CH0/FSPID/FSPIIO5/SUBSPID_15") (pintype "passive"))
    )
    (net (code "35") (name "/GPIO12") (class "Default")
      (node (ref "J1") (pin "15") (pinfunction "15_15") (pintype "passive"))
      (node (ref "U5") (pin "16") (pinfunction "GPIO12/RTC_GPIO12/TOUCH12/ADC2_CH1/FSPICLK/FSPIIO6/SUBSPICLK_16") (pintype "passive"))
    )
    (net (code "36") (name "/GPIO13") (class "Default")
      (node (ref "J1") (pin "16") (pinfunction "16_16") (pintype "passive"))
      (node (ref "U5") (pin "17") (pinfunction "GPIO13/RTC_GPIO13/TOUCH13/ADC2_CH2/FSPIQ/FSPIIO7/SUBSPIQ_17") (pintype "passive"))
    )
    (net (code "37") (name "/GPIO14") (class "Default")
      (node (ref "J1") (pin "17") (pinfunction "17_17") (pintype "passive"))
      (node (ref "U5") (pin "18") (pinfunction "GPIO14/RTC_GPIO14/TOUCH14/ADC2_CH3/FSPIWP/FSPIDQS/SUBSPIWP_18") (pintype "passive"))
    )
    (net (code "38") (name "/GPIO15") (class "Default")
      (node (ref "J1") (pin "18") (pinfunction "18_18") (pintype "passive"))
      (node (ref "U5") (pin "19") (pinfunction "GPIO15/RTC_GPIO15/U0RTS/ADC2_CH4/XTAL_32K_P_19") (pintype "passive"))
    )
    (net (code "39") (name "/GPIO16") (class "Default")
      (node (ref "J1") (pin "19") (pinfunction "19_19") (pintype "passive"))
      (node (ref "U5") (pin "20") (pinfunction "GPIO16/RTC_GPIO16/U0CTS/ADC2_CH5/XTAL_32K_N_20") (pintype "passive"))
    )
    (net (code "40") (name "/GPIO17") (class "Default")
      (node (ref "J1") (pin "20") (pinfunction "20_20") (pintype "passive"))
      (node (ref "U5") (pin "21") (pinfunction "GPIO17/RTC_GPIO17/U1TXD/ADC2_CH6_21") (pintype "passive"))
    )
    (net (code "41") (name "/GPIO18") (class "Default")
      (node (ref "J1") (pin "21") (pinfunction "21_21") (pintype "passive"))
      (node (ref "U5") (pin "22") (pinfunction "GPIO18/RTC_GPIO18/U1RXD/ADC2_CH7/CLK_OUT3_22") (pintype "passive"))
    )
    (net (code "42") (name "/GPIO21") (class "Default")
      (node (ref "J2") (pin "19") (pinfunction "19_19") (pintype "passive"))
      (node (ref "U5") (pin "25") (pinfunction "GPIO21/RTC_GPIO21_25") (pintype "passive"))
    )
    (net (code "43") (name "/GPIO26") (class "Default")
      (node (ref "J2") (pin "18") (pinfunction "18_18") (pintype "passive"))
      (node (ref "U5") (pin "26") (pinfunction "GPIO26/SPICS1_26") (pintype "passive"))
    )
    (net (code "44") (name "/GPIO33") (class "Default")
      (node (ref "J2") (pin "17") (pinfunction "17_17") (pintype "passive"))
      (node (ref "U5") (pin "28") (pinfunction "GPIO33/SPIIO4/FSPIHD/SUBSPIHD_28") (pintype "passive"))
    )
    (net (code "45") (name "/GPIO34") (class "Default")
      (node (ref "J2") (pin "16") (pinfunction "16_16") (pintype "passive"))
      (node (ref "U5") (pin "29") (pinfunction "GPIO34/SPIIO5/FSPICS0/SUBSPICS0_29") (pintype "passive"))
    )
    (net (code "46") (name "/GPIO35") (class "Default")
      (node (ref "J2") (pin "15") (pinfunction "15_15") (pintype "passive"))
      (node (ref "U5") (pin "31") (pinfunction "GPIO35/SPIIO6/FSPID/SUBSPID_31") (pintype "passive"))
    )
    (net (code "47") (name "/GPIO36") (class "Default")
      (node (ref "J2") (pin "14") (pinfunction "14_14") (pintype "passive"))
      (node (ref "U5") (pin "32") (pinfunction "GPIO36/SPIIO7/FSPICLK/SUBSPICLK_32") (pintype "passive"))
    )
    (net (code "48") (name "/GPIO37") (class "Default")
      (node (ref "J2") (pin "13") (pinfunction "13_13") (pintype "passive"))
      (node (ref "U5") (pin "33") (pinfunction "GPIO37/SPIDQS/FSPIQ/SUBSPIQ_33") (pintype "passive"))
    )
    (net (code "49") (name "/GPIO38") (class "Default")
      (node (ref "J2") (pin "12") (pinfunction "12_12") (pintype "passive"))
      (node (ref "U5") (pin "34") (pinfunction "GPIO38/_FSPIWP/SUBSPIWP_34") (pintype "passive"))
    )
    (net (code "50") (name "/GPIO39") (class "Default")
      (node (ref "J2") (pin "11") (pinfunction "11_11") (pintype "passive"))
      (node (ref "U5") (pin "35") (pinfunction "MTCK/GPIO39/CLK_OUT3/SUBSPICS1_35") (pintype "passive"))
    )
    (net (code "51") (name "/GPIO40") (class "Default")
      (node (ref "J2") (pin "10") (pinfunction "10_10") (pintype "passive"))
      (node (ref "U5") (pin "36") (pinfunction "MTDO/GPIO40/CLK_OUT2_36") (pintype "passive"))
    )
    (net (code "52") (name "/GPIO41") (class "Default")
      (node (ref "J2") (pin "9") (pinfunction "9_9") (pintype "passive"))
      (node (ref "U5") (pin "37") (pinfunction "MTDI/GPIO41/CLK_OUT1_37") (pintype "passive"))
    )
    (net (code "53") (name "/GPIO42") (class "Default")
      (node (ref "J2") (pin "8") (pinfunction "8_8") (pintype "passive"))
      (node (ref "U5") (pin "38") (pinfunction "MTMS/GPIO42_38") (pintype "passive"))
    )
    (net (code "54") (name "/GPIO45") (class "Default")
      (node (ref "J2") (pin "5") (pinfunction "5_5") (pintype "passive"))
      (node (ref "U5") (pin "41") (pinfunction "GPIO45_41") (pintype "passive"))
    )
    (net (code "55") (name "/GPIO46") (class "Default")
      (node (ref "J2") (pin "4") (pinfunction "4_4") (pintype "passive"))
      (node (ref "U5") (pin "44") (pinfunction "GPIO46_44") (pintype "passive"))
    )
    (net (code "56") (name "/GPIO47") (class "Default")
      (node (ref "J2") (pin "23") (pinfunction "23_23") (pintype "passive"))
      (node (ref "U5") (pin "27") (pinfunction "GPIO47/SPICLK_P_DIFF/SUBSPICLK_P_DIFF_27") (pintype "passive"))
    )
    (net (code "57") (name "/GPIO48") (class "Default")
      (node (ref "J2") (pin "22") (pinfunction "22_22") (pintype "passive"))
      (node (ref "U5") (pin "30") (pinfunction "GPIO48/SPICLK_N_DIFF/SUBSPICLK_N_DIFF_30") (pintype "passive"))
    )
    (net (code "58") (name "/RTS FTDI") (class "Default")
      (node (ref "Q1") (pin "2") (pinfunction "2_2") (pintype "passive"))
      (node (ref "R22") (pin "2") (pinfunction "2_2") (pintype "passive"))
      (node (ref "U1") (pin "32") (pinfunction "RTS_32") (pintype "passive"))
    )
    (net (code "59") (name "/RXD FTDI") (class "Default")
      (node (ref "R18") (pin "2") (pinfunction "2_2") (pintype "passive"))
      (node (ref "U1") (pin "2") (pinfunction "RXD_2") (pintype "passive"))
    )
    (net (code "60") (name "/TXD FTDI") (class "Default")
      (node (ref "R20") (pin "2") (pinfunction "2_2") (pintype "passive"))
      (node (ref "U1") (pin "30") (pinfunction "TXD_30") (pintype "passive"))
    )
    (net (code "61") (name "/U0RXD") (class "Default")
      (node (ref "J2") (pin "6") (pinfunction "6_6") (pintype "passive"))
      (node (ref "R20") (pin "1") (pinfunction "1_1") (pintype "passive"))
      (node (ref "U5") (pin "40") (pinfunction "U0RXD/GPIO44/CLK_OUT2_40") (pintype "passive"))
    )
    (net (code "62") (name "/U0TXD") (class "Default")
      (node (ref "J2") (pin "7") (pinfunction "7_7") (pintype "passive"))
      (node (ref "R18") (pin "1") (pinfunction "1_1") (pintype "passive"))
      (node (ref "U5") (pin "39") (pinfunction "U0TXD/GPIO43/CLK_OUT1_39") (pintype "passive"))
    )
    (net (code "63") (name "/VBUS SENSE") (class "Default")
      (node (ref "R11") (pin "2") (pinfunction "2_2") (pintype "passive"))
      (node (ref "R7") (pin "1") (pinfunction "1_1") (pintype "passive"))
      (node (ref "U1") (pin "11") (pinfunction "CBUS3_11") (pintype "passive"))
    )
    (net (code "64") (name "GND") (class "Default")
      (node (ref "C1") (pin "1") (pinfunction "1_1") (pintype "passive"))
      (node (ref "C10") (pin "1") (pinfunction "1_1") (pintype "passive"))
      (node (ref "C12") (pin "1") (pinfunction "1_1") (pintype "passive"))
      (node (ref "C13") (pin "1") (pinfunction "1_1") (pintype "passive"))
      (node (ref "C14") (pin "1") (pinfunction "1_1") (pintype "passive"))
      (node (ref "C15") (pin "1") (pinfunction "1_1") (pintype "passive"))
      (node (ref "C16") (pin "1") (pinfunction "1_1") (pintype "passive"))
      (node (ref "C2") (pin "1") (pinfunction "1_1") (pintype "passive"))
      (node (ref "C3") (pin "1") (pinfunction "1_1") (pintype "passive"))
      (node (ref "C4") (pin "1") (pinfunction "1_1") (pintype "passive"))
      (node (ref "C5") (pin "1") (pinfunction "1_1") (pintype "passive"))
      (node (ref "C6") (pin "1") (pinfunction "1_1") (pintype "passive"))
      (node (ref "C7") (pin "1") (pinfunction "1_1") (pintype "passive"))
      (node (ref "C8") (pin "1") (pinfunction "1_1") (pintype "passive"))
      (node (ref "C9") (pin "1") (pinfunction "1_1") (pintype "passive"))
      (node (ref "D1") (pin "A") (pinfunction "A_A") (pintype "passive"))
      (node (ref "D8") (pin "1") (pinfunction "1_1") (pintype "passive"))
      (node (ref "J1") (pin "1") (pinfunction "1_1") (pintype "passive"))
      (node (ref "J1") (pin "23") (pinfunction "23_23") (pintype "passive"))
      (node (ref "J2") (pin "2") (pinfunction "2_2") (pintype "passive"))
      (node (ref "J2") (pin "24") (pinfunction "24_24") (pintype "passive"))
      (node (ref "J3") (pin "A1B12") (pinfunction "GND_A1B12_A1B12") (pintype "passive"))
      (node (ref "J3") (pin "B1A12") (pinfunction "GND_B1A12_B1A12") (pintype "passive"))
      (node (ref "J3") (pin "S1") (pinfunction "SHIELD_1_S1") (pintype "passive"))
      (node (ref "J3") (pin "S2") (pinfunction "SHIELD_2_S2") (pintype "passive"))
      (node (ref "J3") (pin "S3") (pinfunction "SHIELD_3_S3") (pintype "passive"))
      (node (ref "J3") (pin "S4") (pinfunction "SHIELD_4_S4") (pintype "passive"))
      (node (ref "J6") (pin "A1B12") (pinfunction "GND_A1B12_A1B12") (pintype "passive"))
      (node (ref "J6") (pin "B1A12") (pinfunction "GND_B1A12_B1A12") (pintype "passive"))
      (node (ref "J6") (pin "S1") (pinfunction "SHIELD_1_S1") (pintype "passive"))
      (node (ref "J6") (pin "S2") (pinfunction "SHIELD_2_S2") (pintype "passive"))
      (node (ref "J6") (pin "S3") (pinfunction "SHIELD_3_S3") (pintype "passive"))
      (node (ref "J6") (pin "S4") (pinfunction "SHIELD_4_S4") (pintype "passive"))
      (node (ref "R10") (pin "1") (pinfunction "1_1") (pintype "passive"))
      (node (ref "R11") (pin "1") (pinfunction "1_1") (pintype "passive"))
      (node (ref "R12") (pin "1") (pinfunction "1_1") (pintype "passive"))
      (node (ref "R13") (pin "1") (pinfunction "1_1") (pintype "passive"))
      (node (ref "R29") (pin "1") (pinfunction "1_1") (pintype "passive"))
      (node (ref "R30") (pin "1") (pinfunction "1_1") (pintype "passive"))
      (node (ref "R6") (pin "1") (pinfunction "1_1") (pintype "passive"))
      (node (ref "R9") (pin "1") (pinfunction "1_1") (pintype "passive"))
      (node (ref "SW1") (pin "3") (pinfunction "3_3") (pintype "passive"))
      (node (ref "SW1") (pin "4") (pinfunction "4_4") (pintype "passive"))
      (node (ref "SW2") (pin "3") (pinfunction "3_3") (pintype "passive"))
      (node (ref "SW2") (pin "4") (pinfunction "4_4") (pintype "passive"))
      (node (ref "U1") (pin "17") (pinfunction "GND_17") (pintype "passive"))
      (node (ref "U1") (pin "20") (pinfunction "GND_20") (pintype "passive"))
      (node (ref "U1") (pin "24") (pinfunction "AGND_24") (pintype "passive"))
      (node (ref "U1") (pin "26") (pinfunction "TEST_26") (pintype "passive"))
      (node (ref "U1") (pin "33") (pinfunction "EP/GND_33") (pintype "passive"))
      (node (ref "U1") (pin "4") (pinfunction "GND_4") (pintype "passive"))
      (node (ref "U2") (pin "2") (pinfunction "GND_2") (pintype "passive"))
      (node (ref "U3") (pin "2") (pinfunction "GND_2") (pintype "passive"))
      (node (ref "U4") (pin "2") (pinfunction "GND_2") (pintype "passive"))
      (node (ref "U5") (pin "0") (pinfunction "GND_0") (pintype "passive"))
      (node (ref "U5") (pin "42") (pinfunction "GND_42") (pintype "passive"))
      (node (ref "U5") (pin "43") (pinfunction "GND_43") (pintype "passive"))
    )
    (net (code "65") (name "Net-(D7-Pad2)") (class "Default")
      (node (ref "D7") (pin "2") (pinfunction "2_2") (pintype "passive"))
      (node (ref "R15") (pin "1") (pinfunction "1_1") (pintype "passive"))
    )
    (net (code "66") (name "Net-(D8-Pad2)") (class "Default")
      (node (ref "D8") (pin "2") (pinfunction "2_2") (pintype "passive"))
      (node (ref "R14") (pin "1") (pinfunction "1_1") (pintype "passive"))
    )
    (net (code "67") (name "Net-(J3-CC1)") (class "Default")
      (node (ref "J3") (pin "A5") (pinfunction "CC1_A5") (pintype "passive"))
      (node (ref "R10") (pin "2") (pinfunction "2_2") (pintype "passive"))
    )
    (net (code "68") (name "Net-(J3-CC2)") (class "Default")
      (node (ref "J3") (pin "B5") (pinfunction "CC2_B5") (pintype "passive"))
      (node (ref "R9") (pin "2") (pinfunction "2_2") (pintype "passive"))
    )
    (net (code "69") (name "Net-(J6-CC1)") (class "Default")
      (node (ref "J6") (pin "A5") (pinfunction "CC1_A5") (pintype "passive"))
      (node (ref "R13") (pin "2") (pinfunction "2_2") (pintype "passive"))
    )
    (net (code "70") (name "Net-(J6-CC2)") (class "Default")
      (node (ref "J6") (pin "B5") (pinfunction "CC2_B5") (pintype "passive"))
      (node (ref "R12") (pin "2") (pinfunction "2_2") (pintype "passive"))
    )
    (net (code "71") (name "Net-(Q1-Pad1)") (class "Default")
      (node (ref "Q1") (pin "1") (pinfunction "1_1") (pintype "passive"))
      (node (ref "R21") (pin "1") (pinfunction "1_1") (pintype "passive"))
    )
    (net (code "72") (name "Net-(Q2-Pad1)") (class "Default")
      (node (ref "Q2") (pin "1") (pinfunction "1_1") (pintype "passive"))
      (node (ref "R22") (pin "1") (pinfunction "1_1") (pintype "passive"))
    )
    (net (code "73") (name "Net-(U1-CBUS0)") (class "Default")
      (node (ref "R6") (pin "2") (pinfunction "2_2") (pintype "passive"))
      (node (ref "U1") (pin "22") (pinfunction "CBUS0_22") (pintype "passive"))
    )
    (net (code "74") (name "Net-(U2-BST)") (class "Default")
      (node (ref "C11") (pin "2") (pinfunction "2_2") (pintype "passive"))
      (node (ref "U2") (pin "1") (pinfunction "BST_1") (pintype "passive"))
    )
    (net (code "75") (name "Net-(U2-EN)") (class "Default")
      (node (ref "R27") (pin "1") (pinfunction "1_1") (pintype "passive"))
      (node (ref "R29") (pin "2") (pinfunction "2_2") (pintype "passive"))
      (node (ref "U2") (pin "4") (pinfunction "EN_4") (pintype "passive"))
    )
    (net (code "76") (name "Net-(U2-FB)") (class "Default")
      (node (ref "R28") (pin "1") (pinfunction "1_1") (pintype "passive"))
      (node (ref "R30") (pin "2") (pinfunction "2_2") (pintype "passive"))
      (node (ref "U2") (pin "3") (pinfunction "FB_3") (pintype "passive"))
    )
    (net (code "77") (name "Net-(U2-SW)") (class "Default")
      (node (ref "C11") (pin "1") (pinfunction "1_1") (pintype "passive"))
      (node (ref "D1") (pin "K") (pinfunction "K_K") (pintype "passive"))
      (node (ref "L1") (pin "1") (pinfunction "1_1") (pintype "passive"))
      (node (ref "U2") (pin "6") (pinfunction "SW_6") (pintype "passive"))
    )
    (net (code "78") (name "unconnected-(J1-Pad24)") (class "Default")
      (node (ref "J1") (pin "24") (pinfunction "24_24") (pintype "passive+no_connect"))
    )
    (net (code "79") (name "unconnected-(J3-SBU1-PadA8)") (class "Default")
      (node (ref "J3") (pin "A8") (pinfunction "SBU1_A8") (pintype "passive+no_connect"))
    )
    (net (code "80") (name "unconnected-(J3-SBU2-PadB8)") (class "Default")
      (node (ref "J3") (pin "B8") (pinfunction "SBU2_B8") (pintype "passive+no_connect"))
    )
    (net (code "81") (name "unconnected-(J6-SBU1-PadA8)") (class "Default")
      (node (ref "J6") (pin "A8") (pinfunction "SBU1_A8") (pintype "passive+no_connect"))
    )
    (net (code "82") (name "unconnected-(J6-SBU2-PadB8)") (class "Default")
      (node (ref "J6") (pin "B8") (pinfunction "SBU2_B8") (pintype "passive+no_connect"))
    )
    (net (code "83") (name "unconnected-(U1-CBUS1-Pad21)") (class "Default")
      (node (ref "U1") (pin "21") (pinfunction "CBUS1_21") (pintype "passive+no_connect"))
    )
    (net (code "84") (name "unconnected-(U1-CBUS2-Pad10)") (class "Default")
      (node (ref "U1") (pin "10") (pinfunction "CBUS2_10") (pintype "passive+no_connect"))
    )
    (net (code "85") (name "unconnected-(U1-CBUS4-Pad9)") (class "Default")
      (node (ref "U1") (pin "9") (pinfunction "CBUS4_9") (pintype "passive+no_connect"))
    )
    (net (code "86") (name "unconnected-(U1-CTS-Pad8)") (class "Default")
      (node (ref "U1") (pin "8") (pinfunction "CTS_8") (pintype "passive+no_connect"))
    )
    (net (code "87") (name "unconnected-(U1-DCD-Pad7)") (class "Default")
      (node (ref "U1") (pin "7") (pinfunction "DCD_7") (pintype "passive+no_connect"))
    )
    (net (code "88") (name "unconnected-(U1-DSR-Pad6)") (class "Default")
      (node (ref "U1") (pin "6") (pinfunction "DSR_6") (pintype "passive+no_connect"))
    )
    (net (code "89") (name "unconnected-(U1-NC-Pad5)") (class "Default")
      (node (ref "U1") (pin "5") (pinfunction "NC_5") (pintype "passive"))
    )
    (net (code "90") (name "unconnected-(U1-NC-Pad12)") (class "Default")
      (node (ref "U1") (pin "12") (pinfunction "NC_12") (pintype "passive"))
    )
    (net (code "91") (name "unconnected-(U1-NC-Pad13)") (class "Default")
      (node (ref "U1") (pin "13") (pinfunction "NC_13") (pintype "passive"))
    )
    (net (code "92") (name "unconnected-(U1-NC-Pad23)") (class "Default")
      (node (ref "U1") (pin "23") (pinfunction "NC_23") (pintype "passive"))
    )
    (net (code "93") (name "unconnected-(U1-NC-Pad25)") (class "Default")
      (node (ref "U1") (pin "25") (pinfunction "NC_25") (pintype "passive"))
    )
    (net (code "94") (name "unconnected-(U1-NC-Pad29)") (class "Default")
      (node (ref "U1") (pin "29") (pinfunction "NC_29") (pintype "passive"))
    )
    (net (code "95") (name "unconnected-(U1-OSCI-Pad27)") (class "Default")
      (node (ref "U1") (pin "27") (pinfunction "OSCI_27") (pintype "passive"))
    )
    (net (code "96") (name "unconnected-(U1-OSCO-Pad28)") (class "Default")
      (node (ref "U1") (pin "28") (pinfunction "OSCO_28") (pintype "passive"))
    )
    (net (code "97") (name "unconnected-(U1-RI-Pad3)") (class "Default")
      (node (ref "U1") (pin "3") (pinfunction "RI_3") (pintype "passive+no_connect"))
    )
    (net (code "98") (name "unconnected-(U3-IO1-Pad1)") (class "Default")
      (node (ref "U3") (pin "1") (pinfunction "IO1_1") (pintype "passive"))
    )
    (net (code "99") (name "unconnected-(U3-IO2-Pad3)") (class "Default")
      (node (ref "U3") (pin "3") (pinfunction "IO2_3") (pintype "passive"))
    )
    (net (code "100") (name "unconnected-(U4-IO1-Pad1)") (class "Default")
      (node (ref "U4") (pin "1") (pinfunction "IO1_1") (pintype "passive"))
    )
    (net (code "101") (name "unconnected-(U4-IO2-Pad3)") (class "Default")
      (node (ref "U4") (pin "3") (pinfunction "IO2_3") (pintype "passive"))
    )
  )
)
